# Sheet1.net
KiCad netlist of a schematic drawn in Altium Designer
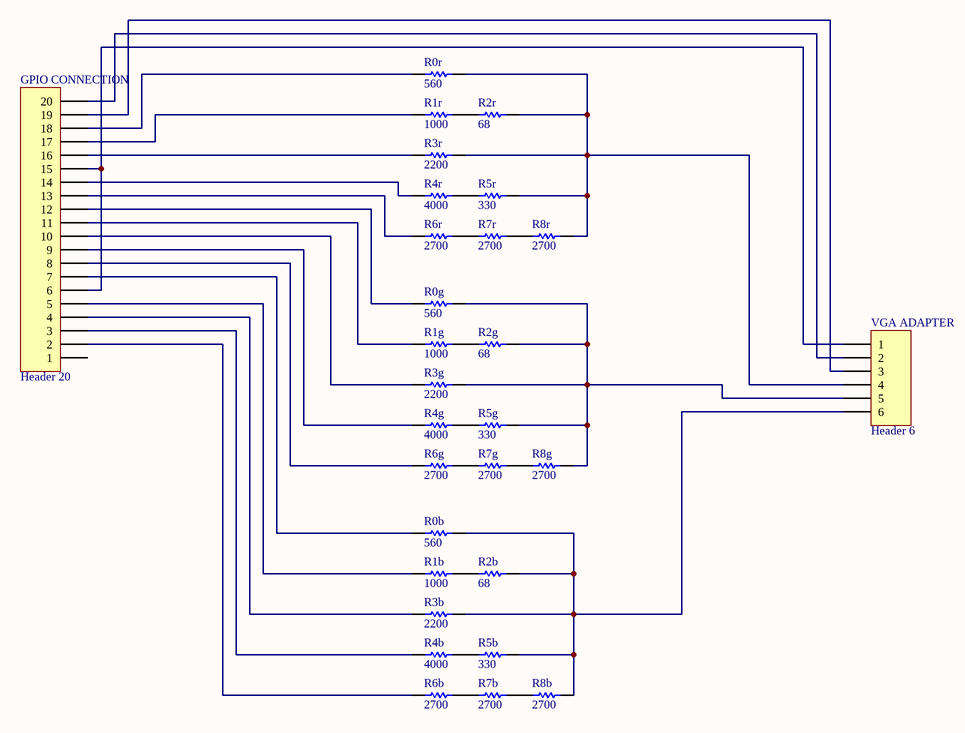
[diagram p0: Sheet1.SchDoc]

(export (version "E")
  (design (tool "Eeschema 10.0.6"))
  (components
    (comp (ref "GPIO CONNECTION")
      (value "Header 20")
      (footprint "HDR1X20")
      (description "Header, 20-Pin")
      (fields (field (name "PUBLISHER") "Altium Limited"))
      (libsource (lib "Miscellaneous Connectors") (part "Header 20"))
    )
    (comp (ref "R0b") (value "560") (footprint "RES400") (libsource (lib "LIBEBAL") (part "RES")))
    (comp (ref "R0g") (value "560") (footprint "RES400") (libsource (lib "LIBEBAL") (part "RES")))
    (comp (ref "R0r") (value "560") (footprint "RES400") (libsource (lib "LIBEBAL") (part "RES")))
    (comp (ref "R1b") (value "1000") (footprint "RES400") (libsource (lib "LIBEBAL") (part "RES")))
    (comp (ref "R1g") (value "1000") (footprint "RES400") (libsource (lib "LIBEBAL") (part "RES")))
    (comp (ref "R1r") (value "1000") (footprint "RES400") (libsource (lib "LIBEBAL") (part "RES")))
    (comp (ref "R2b") (value "68") (footprint "RES400") (libsource (lib "LIBEBAL") (part "RES")))
    (comp (ref "R2g") (value "68") (footprint "RES400") (libsource (lib "LIBEBAL") (part "RES")))
    (comp (ref "R2r") (value "68") (footprint "RES400") (libsource (lib "LIBEBAL") (part "RES")))
    (comp (ref "R3b") (value "2200") (footprint "RES400") (libsource (lib "LIBEBAL") (part "RES")))
    (comp (ref "R3g") (value "2200") (footprint "RES400") (libsource (lib "LIBEBAL") (part "RES")))
    (comp (ref "R3r") (value "2200") (footprint "RES400") (libsource (lib "LIBEBAL") (part "RES")))
    (comp (ref "R4b") (value "4000") (footprint "RES400") (libsource (lib "LIBEBAL") (part "RES")))
    (comp (ref "R4g") (value "4000") (footprint "RES400") (libsource (lib "LIBEBAL") (part "RES")))
    (comp (ref "R4r") (value "4000") (footprint "RES400") (libsource (lib "LIBEBAL") (part "RES")))
    (comp (ref "R5b") (value "330") (footprint "RES400") (libsource (lib "LIBEBAL") (part "RES")))
    (comp (ref "R5g") (value "330") (footprint "RES400") (libsource (lib "LIBEBAL") (part "RES")))
    (comp (ref "R5r") (value "330") (footprint "RES400") (libsource (lib "LIBEBAL") (part "RES")))
    (comp (ref "R6b") (value "2700") (footprint "RES400") (libsource (lib "LIBEBAL") (part "RES")))
    (comp (ref "R6g") (value "2700") (footprint "RES400") (libsource (lib "LIBEBAL") (part "RES")))
    (comp (ref "R6r") (value "2700") (footprint "RES400") (libsource (lib "LIBEBAL") (part "RES")))
    (comp (ref "R7b") (value "2700") (footprint "RES400") (libsource (lib "LIBEBAL") (part "RES")))
    (comp (ref "R7g") (value "2700") (footprint "RES400") (libsource (lib "LIBEBAL") (part "RES")))
    (comp (ref "R7r") (value "2700") (footprint "RES400") (libsource (lib "LIBEBAL") (part "RES")))
    (comp (ref "R8b") (value "2700") (footprint "RES400") (libsource (lib "LIBEBAL") (part "RES")))
    (comp (ref "R8g") (value "2700") (footprint "RES400") (libsource (lib "LIBEBAL") (part "RES")))
    (comp (ref "R8r") (value "2700") (footprint "RES400") (libsource (lib "LIBEBAL") (part "RES")))
    (comp (ref "VGA ADAPTER")
      (value "Header 6")
      (footprint "HDR1X6")
      (description "Header, 6-Pin")
      (fields (field (name "PUBLISHER") "Altium Limited"))
      (libsource (lib "Miscellaneous Connectors") (part "Header 6"))
    )
  )
  (nets
    (net (code "1") (name "Net-(GPIO CONNECTION-Pad2)") (class "Default")
      (node (ref "GPIO CONNECTION") (pin "2") (pinfunction "2_2") (pintype "passive"))
      (node (ref "R6b") (pin "1") (pinfunction "1_1") (pintype "passive"))
    )
    (net (code "2") (name "Net-(GPIO CONNECTION-Pad3)") (class "Default")
      (node (ref "GPIO CONNECTION") (pin "3") (pinfunction "3_3") (pintype "passive"))
      (node (ref "R4b") (pin "1") (pinfunction "1_1") (pintype "passive"))
    )
    (net (code "3") (name "Net-(GPIO CONNECTION-Pad4)") (class "Default")
      (node (ref "GPIO CONNECTION") (pin "4") (pinfunction "4_4") (pintype "passive"))
      (node (ref "R3b") (pin "1") (pinfunction "1_1") (pintype "passive"))
    )
    (net (code "4") (name "Net-(GPIO CONNECTION-Pad5)") (class "Default")
      (node (ref "GPIO CONNECTION") (pin "5") (pinfunction "5_5") (pintype "passive"))
      (node (ref "R1b") (pin "1") (pinfunction "1_1") (pintype "passive"))
    )
    (net (code "5") (name "Net-(GPIO CONNECTION-Pad7)") (class "Default")
      (node (ref "GPIO CONNECTION") (pin "7") (pinfunction "7_7") (pintype "passive"))
      (node (ref "R0b") (pin "1") (pinfunction "1_1") (pintype "passive"))
    )
    (net (code "6") (name "Net-(GPIO CONNECTION-Pad8)") (class "Default")
      (node (ref "GPIO CONNECTION") (pin "8") (pinfunction "8_8") (pintype "passive"))
      (node (ref "R6g") (pin "1") (pinfunction "1_1") (pintype "passive"))
    )
    (net (code "7") (name "Net-(GPIO CONNECTION-Pad9)") (class "Default")
      (node (ref "GPIO CONNECTION") (pin "9") (pinfunction "9_9") (pintype "passive"))
      (node (ref "R4g") (pin "1") (pinfunction "1_1") (pintype "passive"))
    )
    (net (code "8") (name "Net-(GPIO CONNECTION-Pad10)") (class "Default")
      (node (ref "GPIO CONNECTION") (pin "10") (pinfunction "10_10") (pintype "passive"))
      (node (ref "R3g") (pin "1") (pinfunction "1_1") (pintype "passive"))
    )
    (net (code "9") (name "Net-(GPIO CONNECTION-Pad11)") (class "Default")
      (node (ref "GPIO CONNECTION") (pin "11") (pinfunction "11_11") (pintype "passive"))
      (node (ref "R1g") (pin "1") (pinfunction "1_1") (pintype "passive"))
    )
    (net (code "10") (name "Net-(GPIO CONNECTION-Pad12)") (class "Default")
      (node (ref "GPIO CONNECTION") (pin "12") (pinfunction "12_12") (pintype "passive"))
      (node (ref "R0g") (pin "1") (pinfunction "1_1") (pintype "passive"))
    )
    (net (code "11") (name "Net-(GPIO CONNECTION-Pad13)") (class "Default")
      (node (ref "GPIO CONNECTION") (pin "13") (pinfunction "13_13") (pintype "passive"))
      (node (ref "R6r") (pin "1") (pinfunction "1_1") (pintype "passive"))
    )
    (net (code "12") (name "Net-(GPIO CONNECTION-Pad14)") (class "Default")
      (node (ref "GPIO CONNECTION") (pin "14") (pinfunction "14_14") (pintype "passive"))
      (node (ref "R4r") (pin "1") (pinfunction "1_1") (pintype "passive"))
    )
    (net (code "13") (name "Net-(GPIO CONNECTION-Pad15)") (class "Default")
      (node (ref "GPIO CONNECTION") (pin "15") (pinfunction "15_15") (pintype "passive"))
      (node (ref "GPIO CONNECTION") (pin "6") (pinfunction "6_6") (pintype "passive"))
      (node (ref "VGA ADAPTER") (pin "1") (pinfunction "1_1") (pintype "passive"))
    )
    (net (code "14") (name "Net-(GPIO CONNECTION-Pad16)") (class "Default")
      (node (ref "GPIO CONNECTION") (pin "16") (pinfunction "16_16") (pintype "passive"))
      (node (ref "R3r") (pin "1") (pinfunction "1_1") (pintype "passive"))
    )
    (net (code "15") (name "Net-(GPIO CONNECTION-Pad17)") (class "Default")
      (node (ref "GPIO CONNECTION") (pin "17") (pinfunction "17_17") (pintype "passive"))
      (node (ref "R1r") (pin "1") (pinfunction "1_1") (pintype "passive"))
    )
    (net (code "16") (name "Net-(GPIO CONNECTION-Pad18)") (class "Default")
      (node (ref "GPIO CONNECTION") (pin "18") (pinfunction "18_18") (pintype "passive"))
      (node (ref "R0r") (pin "1") (pinfunction "1_1") (pintype "passive"))
    )
    (net (code "17") (name "Net-(GPIO CONNECTION-Pad19)") (class "Default")
      (node (ref "GPIO CONNECTION") (pin "19") (pinfunction "19_19") (pintype "passive"))
      (node (ref "VGA ADAPTER") (pin "3") (pinfunction "3_3") (pintype "passive"))
    )
    (net (code "18") (name "Net-(GPIO CONNECTION-Pad20)") (class "Default")
      (node (ref "GPIO CONNECTION") (pin "20") (pinfunction "20_20") (pintype "passive"))
      (node (ref "VGA ADAPTER") (pin "2") (pinfunction "2_2") (pintype "passive"))
    )
    (net (code "19") (name "Net-(R0b-Pad2)") (class "Default")
      (node (ref "R0b") (pin "2") (pinfunction "2_2") (pintype "passive"))
      (node (ref "R2b") (pin "2") (pinfunction "2_2") (pintype "passive"))
      (node (ref "R3b") (pin "2") (pinfunction "2_2") (pintype "passive"))
      (node (ref "R5b") (pin "2") (pinfunction "2_2") (pintype "passive"))
      (node (ref "R8b") (pin "2") (pinfunction "2_2") (pintype "passive"))
      (node (ref "VGA ADAPTER") (pin "6") (pinfunction "6_6") (pintype "passive"))
    )
    (net (code "20") (name "Net-(R0g-Pad2)") (class "Default")
      (node (ref "R0g") (pin "2") (pinfunction "2_2") (pintype "passive"))
      (node (ref "R2g") (pin "2") (pinfunction "2_2") (pintype "passive"))
      (node (ref "R3g") (pin "2") (pinfunction "2_2") (pintype "passive"))
      (node (ref "R5g") (pin "2") (pinfunction "2_2") (pintype "passive"))
      (node (ref "R8g") (pin "2") (pinfunction "2_2") (pintype "passive"))
      (node (ref "VGA ADAPTER") (pin "5") (pinfunction "5_5") (pintype "passive"))
    )
    (net (code "21") (name "Net-(R0r-Pad2)") (class "Default")
      (node (ref "R0r") (pin "2") (pinfunction "2_2") (pintype "passive"))
      (node (ref "R2r") (pin "2") (pinfunction "2_2") (pintype "passive"))
      (node (ref "R3r") (pin "2") (pinfunction "2_2") (pintype "passive"))
      (node (ref "R5r") (pin "2") (pinfunction "2_2") (pintype "passive"))
      (node (ref "R8r") (pin "2") (pinfunction "2_2") (pintype "passive"))
      (node (ref "VGA ADAPTER") (pin "4") (pinfunction "4_4") (pintype "passive"))
    )
    (net (code "22") (name "Net-(R1b-Pad2)") (class "Default")
      (node (ref "R1b") (pin "2") (pinfunction "2_2") (pintype "passive"))
      (node (ref "R2b") (pin "1") (pinfunction "1_1") (pintype "passive"))
    )
    (net (code "23") (name "Net-(R1g-Pad2)") (class "Default")
      (node (ref "R1g") (pin "2") (pinfunction "2_2") (pintype "passive"))
      (node (ref "R2g") (pin "1") (pinfunction "1_1") (pintype "passive"))
    )
    (net (code "24") (name "Net-(R1r-Pad2)") (class "Default")
      (node (ref "R1r") (pin "2") (pinfunction "2_2") (pintype "passive"))
      (node (ref "R2r") (pin "1") (pinfunction "1_1") (pintype "passive"))
    )
    (net (code "25") (name "Net-(R4b-Pad2)") (class "Default")
      (node (ref "R4b") (pin "2") (pinfunction "2_2") (pintype "passive"))
      (node (ref "R5b") (pin "1") (pinfunction "1_1") (pintype "passive"))
    )
    (net (code "26") (name "Net-(R4g-Pad2)") (class "Default")
      (node (ref "R4g") (pin "2") (pinfunction "2_2") (pintype "passive"))
      (node (ref "R5g") (pin "1") (pinfunction "1_1") (pintype "passive"))
    )
    (net (code "27") (name "Net-(R4r-Pad2)") (class "Default")
      (node (ref "R4r") (pin "2") (pinfunction "2_2") (pintype "passive"))
      (node (ref "R5r") (pin "1") (pinfunction "1_1") (pintype "passive"))
    )
    (net (code "28") (name "Net-(R6b-Pad2)") (class "Default")
      (node (ref "R6b") (pin "2") (pinfunction "2_2") (pintype "passive"))
      (node (ref "R7b") (pin "1") (pinfunction "1_1") (pintype "passive"))
    )
    (net (code "29") (name "Net-(R6g-Pad2)") (class "Default")
      (node (ref "R6g") (pin "2") (pinfunction "2_2") (pintype "passive"))
      (node (ref "R7g") (pin "1") (pinfunction "1_1") (pintype "passive"))
    )
    (net (code "30") (name "Net-(R6r-Pad2)") (class "Default")
      (node (ref "R6r") (pin "2") (pinfunction "2_2") (pintype "passive"))
      (node (ref "R7r") (pin "1") (pinfunction "1_1") (pintype "passive"))
    )
    (net (code "31") (name "Net-(R7b-Pad2)") (class "Default")
      (node (ref "R7b") (pin "2") (pinfunction "2_2") (pintype "passive"))
      (node (ref "R8b") (pin "1") (pinfunction "1_1") (pintype "passive"))
    )
    (net (code "32") (name "Net-(R7g-Pad2)") (class "Default")
      (node (ref "R7g") (pin "2") (pinfunction "2_2") (pintype "passive"))
      (node (ref "R8g") (pin "1") (pinfunction "1_1") (pintype "passive"))
    )
    (net (code "33") (name "Net-(R7r-Pad2)") (class "Default")
      (node (ref "R7r") (pin "2") (pinfunction "2_2") (pintype "passive"))
      (node (ref "R8r") (pin "1") (pinfunction "1_1") (pintype "passive"))
    )
    (net (code "34") (name "unconnected-(GPIO CONNECTION-Pad1)") (class "Default")
      (node (ref "GPIO CONNECTION") (pin "1") (pinfunction "1_1") (pintype "passive"))
    )
  )
)
